# bodenfeuchte.net
KiCad netlist of a schematic drawn in EAGLE
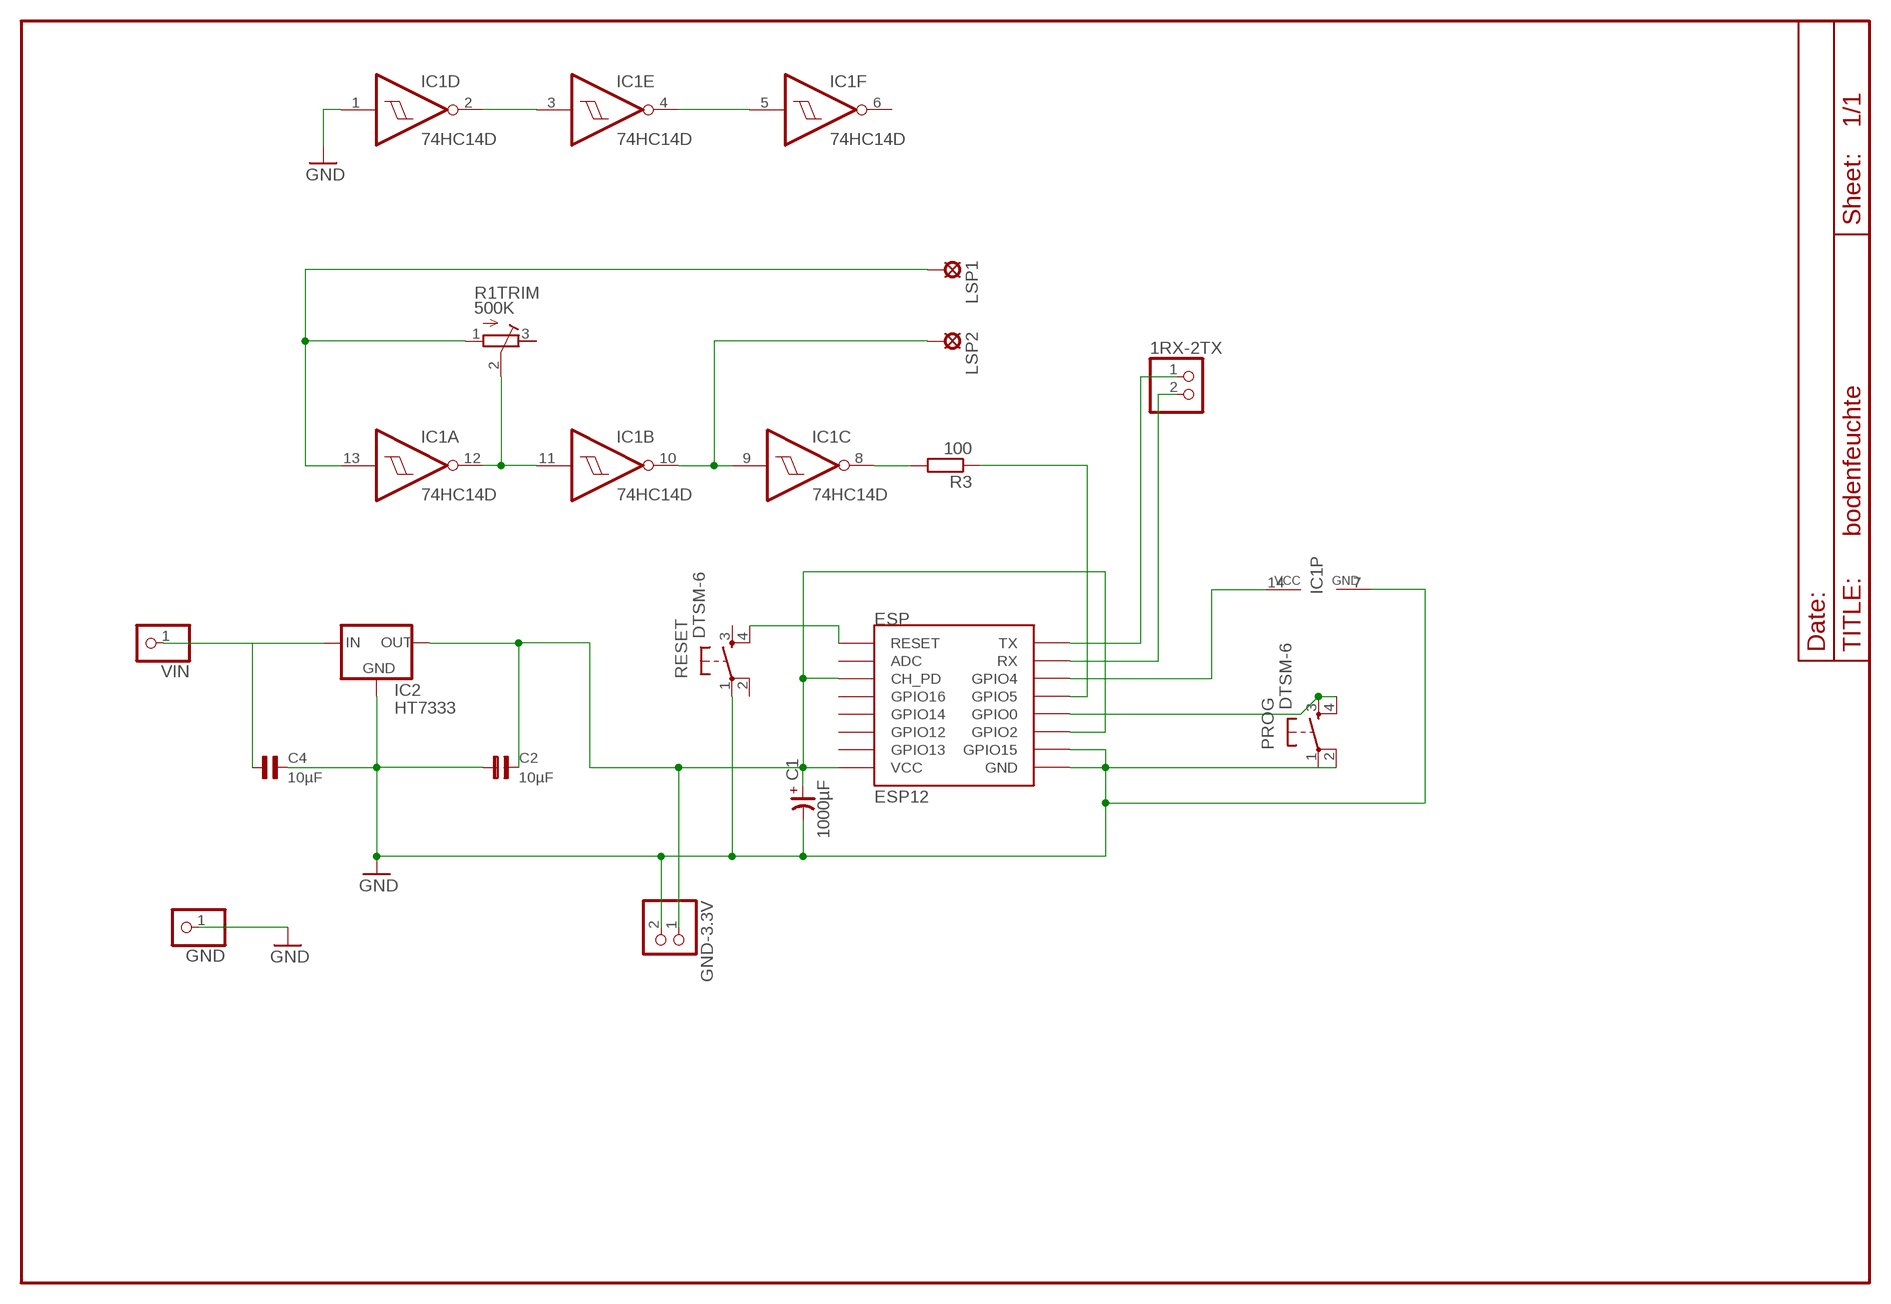
[diagram p0: schematic, sheet 1]

(export (version "E")
  (design (tool "Eeschema 10.0.6"))
  (components
    (comp (ref "1RX-2TX")
      (value "PINHD-1X2")
      (footprint "eagle-import:1X02")
      (libsource (lib "eagle-import") (part "PINHD-1X2"))
    )
    (comp (ref "C1")
      (value "1000µF")
      (footprint "eagle-import:SV-E_F")
      (libsource (lib "eagle-import") (part "CP-SV-E/F"))
    )
    (comp (ref "C2")
      (value "10µF")
      (footprint "eagle-import:1206")
      (libsource (lib "eagle-import") (part "C1206"))
    )
    (comp (ref "C4")
      (value "10µF")
      (footprint "eagle-import:1206")
      (libsource (lib "eagle-import") (part "C1206"))
    )
    (comp (ref "ESP")
      (value "ESP12")
      (footprint "eagle-import:ESP12")
      (libsource (lib "eagle-import") (part "ESP12"))
    )
    (comp (ref "GND")
      (value "PINHD-1X1")
      (footprint "eagle-import:1X01")
      (libsource (lib "eagle-import") (part "PINHD-1X1"))
    )
    (comp (ref "GND-3.3V")
      (value "PINHD-1X2")
      (footprint "eagle-import:1X02")
      (libsource (lib "eagle-import") (part "PINHD-1X2"))
    )
    (comp (ref "IC1")
      (value "74HC14D")
      (footprint "eagle-import:SO14")
      (libsource (lib "eagle-import") (part "7414DHC"))
    )
    (comp (ref "IC2")
      (value "HT7333")
      (footprint "eagle-import:SOT-89")
      (libsource (lib "eagle-import") (part "HT7333"))
    )
    (comp (ref "LSP1")
      (value "LSP11")
      (footprint "eagle-import:LSP11")
      (libsource (lib "eagle-import") (part "LSP11"))
    )
    (comp (ref "LSP2")
      (value "LSP11")
      (footprint "eagle-import:LSP11")
      (libsource (lib "eagle-import") (part "LSP11"))
    )
    (comp (ref "PROG")
      (value "DTSM-6")
      (footprint "eagle-import:DTSM-6")
      (libsource (lib "eagle-import") (part "DTSM-6"))
    )
    (comp (ref "R1TRIM")
      (value "500K")
      (footprint "eagle-import:RTRIM3374")
      (libsource (lib "eagle-import") (part "R-TRIMM3374"))
    )
    (comp (ref "R3")
      (value "100")
      (footprint "eagle-import:R0603")
      (libsource (lib "eagle-import") (part "R-EU_R0603"))
    )
    (comp (ref "RESET")
      (value "DTSM-6")
      (footprint "eagle-import:DTSM-6")
      (libsource (lib "eagle-import") (part "DTSM-6"))
    )
    (comp (ref "VIN")
      (value "PINHD-1X1")
      (footprint "eagle-import:1X01")
      (libsource (lib "eagle-import") (part "PINHD-1X1"))
    )
  )
  (nets
    (net (code "1") (name "/N$9") (class "Default")
      (node (ref "ESP") (pin "GPIO0") (pinfunction "GPIO0_GPIO0") (pintype "bidirectional"))
      (node (ref "IC1") (pin "13") (pinfunction "I_13") (pintype "input"))
      (node (ref "LSP1") (pin "MP") (pinfunction "MP_MP") (pintype "passive"))
      (node (ref "PROG") (pin "3") (pinfunction "3_3") (pintype "passive"))
      (node (ref "PROG") (pin "4") (pinfunction "4_4") (pintype "passive"))
      (node (ref "R1TRIM") (pin "1") (pinfunction "A_1") (pintype "passive"))
    )
    (net (code "2") (name "GND") (class "Default")
      (node (ref "C1") (pin "-") (pinfunction "-_-") (pintype "passive"))
      (node (ref "C2") (pin "1") (pinfunction "1_1") (pintype "passive"))
      (node (ref "C4") (pin "2") (pinfunction "2_2") (pintype "passive"))
      (node (ref "ESP") (pin "GND") (pinfunction "GND_GND") (pintype "bidirectional"))
      (node (ref "ESP") (pin "GPIO15") (pinfunction "GPIO15_GPIO15") (pintype "bidirectional"))
      (node (ref "GND") (pin "1") (pinfunction "1_1") (pintype "passive"))
      (node (ref "GND-3.3V") (pin "2") (pinfunction "2_2") (pintype "passive"))
      (node (ref "IC1") (pin "1") (pinfunction "I_1") (pintype "input"))
      (node (ref "IC1") (pin "7") (pinfunction "GND_7") (pintype "power_in"))
      (node (ref "IC2") (pin "2") (pinfunction "GND_2") (pintype "input"))
      (node (ref "PROG") (pin "1") (pinfunction "1_1") (pintype "passive"))
      (node (ref "PROG") (pin "2") (pinfunction "2_2") (pintype "passive"))
      (node (ref "RESET") (pin "1") (pinfunction "1_1") (pintype "passive"))
    )
    (net (code "3") (name "Net-(1RX-2TX-Pad1)") (class "Default")
      (node (ref "1RX-2TX") (pin "1") (pinfunction "1_1") (pintype "passive"))
      (node (ref "ESP") (pin "TX") (pinfunction "TX_TX") (pintype "bidirectional"))
    )
    (net (code "4") (name "Net-(1RX-2TX-Pad2)") (class "Default")
      (node (ref "1RX-2TX") (pin "2") (pinfunction "2_2") (pintype "passive"))
      (node (ref "ESP") (pin "RX") (pinfunction "RX_RX") (pintype "bidirectional"))
    )
    (net (code "5") (name "Net-(C4-Pad1)") (class "Default")
      (node (ref "C4") (pin "1") (pinfunction "1_1") (pintype "passive"))
      (node (ref "IC2") (pin "3") (pinfunction "IN_3") (pintype "input"))
      (node (ref "IC2") (pin "4") (pinfunction "IN_4") (pintype "input"))
      (node (ref "VIN") (pin "1") (pinfunction "1_1") (pintype "passive"))
    )
    (net (code "6") (name "Net-(ESP-PadGPIO5)") (class "Default")
      (node (ref "ESP") (pin "GPIO5") (pinfunction "GPIO5_GPIO5") (pintype "bidirectional"))
      (node (ref "R3") (pin "1") (pinfunction "1_1") (pintype "passive"))
    )
    (net (code "7") (name "Net-(ESP-PadRESET)") (class "Default")
      (node (ref "ESP") (pin "RESET") (pinfunction "RESET_RESET") (pintype "bidirectional"))
      (node (ref "RESET") (pin "4") (pinfunction "4_4") (pintype "passive"))
    )
    (net (code "8") (name "Net-(IC1A-O)") (class "Default")
      (node (ref "IC1") (pin "11") (pinfunction "I_11") (pintype "input"))
      (node (ref "IC1") (pin "12") (pinfunction "O_12") (pintype "output"))
      (node (ref "R1TRIM") (pin "2") (pinfunction "S_2") (pintype "passive"))
    )
    (net (code "9") (name "Net-(IC1B-O)") (class "Default")
      (node (ref "IC1") (pin "10") (pinfunction "O_10") (pintype "output"))
      (node (ref "IC1") (pin "9") (pinfunction "I_9") (pintype "input"))
      (node (ref "LSP2") (pin "MP") (pinfunction "MP_MP") (pintype "passive"))
    )
    (net (code "10") (name "Net-(IC1C-O)") (class "Default")
      (node (ref "IC1") (pin "8") (pinfunction "O_8") (pintype "output"))
      (node (ref "R3") (pin "2") (pinfunction "2_2") (pintype "passive"))
    )
    (net (code "11") (name "Net-(IC1D-O)") (class "Default")
      (node (ref "IC1") (pin "2") (pinfunction "O_2") (pintype "output"))
      (node (ref "IC1") (pin "3") (pinfunction "I_3") (pintype "input"))
    )
    (net (code "12") (name "Net-(IC1E-O)") (class "Default")
      (node (ref "IC1") (pin "4") (pinfunction "O_4") (pintype "output"))
      (node (ref "IC1") (pin "5") (pinfunction "I_5") (pintype "input"))
    )
    (net (code "13") (name "Net-(IC1G-VCC)") (class "Default")
      (node (ref "ESP") (pin "GPIO4") (pinfunction "GPIO4_GPIO4") (pintype "bidirectional"))
      (node (ref "IC1") (pin "14") (pinfunction "VCC_14") (pintype "power_in"))
    )
    (net (code "14") (name "Net-(IC2-OUT)") (class "Default")
      (node (ref "C1") (pin "+") (pinfunction "+_+") (pintype "passive"))
      (node (ref "C2") (pin "2") (pinfunction "2_2") (pintype "passive"))
      (node (ref "ESP") (pin "CH_PD") (pinfunction "CH_PD_CH_PD") (pintype "bidirectional"))
      (node (ref "ESP") (pin "GPIO2") (pinfunction "GPIO2_GPIO2") (pintype "bidirectional"))
      (node (ref "ESP") (pin "VCC") (pinfunction "VCC_VCC") (pintype "bidirectional"))
      (node (ref "GND-3.3V") (pin "1") (pinfunction "1_1") (pintype "passive"))
      (node (ref "IC2") (pin "1") (pinfunction "OUT_1") (pintype "passive"))
    )
    (net (code "15") (name "unconnected-(ESP-PadADC)") (class "Default")
      (node (ref "ESP") (pin "ADC") (pinfunction "ADC_ADC") (pintype "bidirectional"))
    )
    (net (code "16") (name "unconnected-(ESP-PadGPIO12)") (class "Default")
      (node (ref "ESP") (pin "GPIO12") (pinfunction "GPIO12_GPIO12") (pintype "bidirectional"))
    )
    (net (code "17") (name "unconnected-(ESP-PadGPIO13)") (class "Default")
      (node (ref "ESP") (pin "GPIO13") (pinfunction "GPIO13_GPIO13") (pintype "bidirectional"))
    )
    (net (code "18") (name "unconnected-(ESP-PadGPIO14)") (class "Default")
      (node (ref "ESP") (pin "GPIO14") (pinfunction "GPIO14_GPIO14") (pintype "bidirectional"))
    )
    (net (code "19") (name "unconnected-(ESP-PadGPIO16)") (class "Default")
      (node (ref "ESP") (pin "GPIO16") (pinfunction "GPIO16_GPIO16") (pintype "bidirectional"))
    )
    (net (code "20") (name "unconnected-(IC1F-O-Pad6)") (class "Default")
      (node (ref "IC1") (pin "6") (pinfunction "O_6") (pintype "output"))
    )
    (net (code "21") (name "unconnected-(R1TRIM-E-Pad3)") (class "Default")
      (node (ref "R1TRIM") (pin "3") (pinfunction "E_3") (pintype "passive"))
    )
    (net (code "22") (name "unconnected-(RESET-Pad2)") (class "Default")
      (node (ref "RESET") (pin "2") (pinfunction "2_2") (pintype "passive"))
    )
    (net (code "23") (name "unconnected-(RESET-Pad3)") (class "Default")
      (node (ref "RESET") (pin "3") (pinfunction "3_3") (pintype "passive"))
    )
  )
)
